# main.net
KiCad netlist of a schematic drawn in Altium Designer
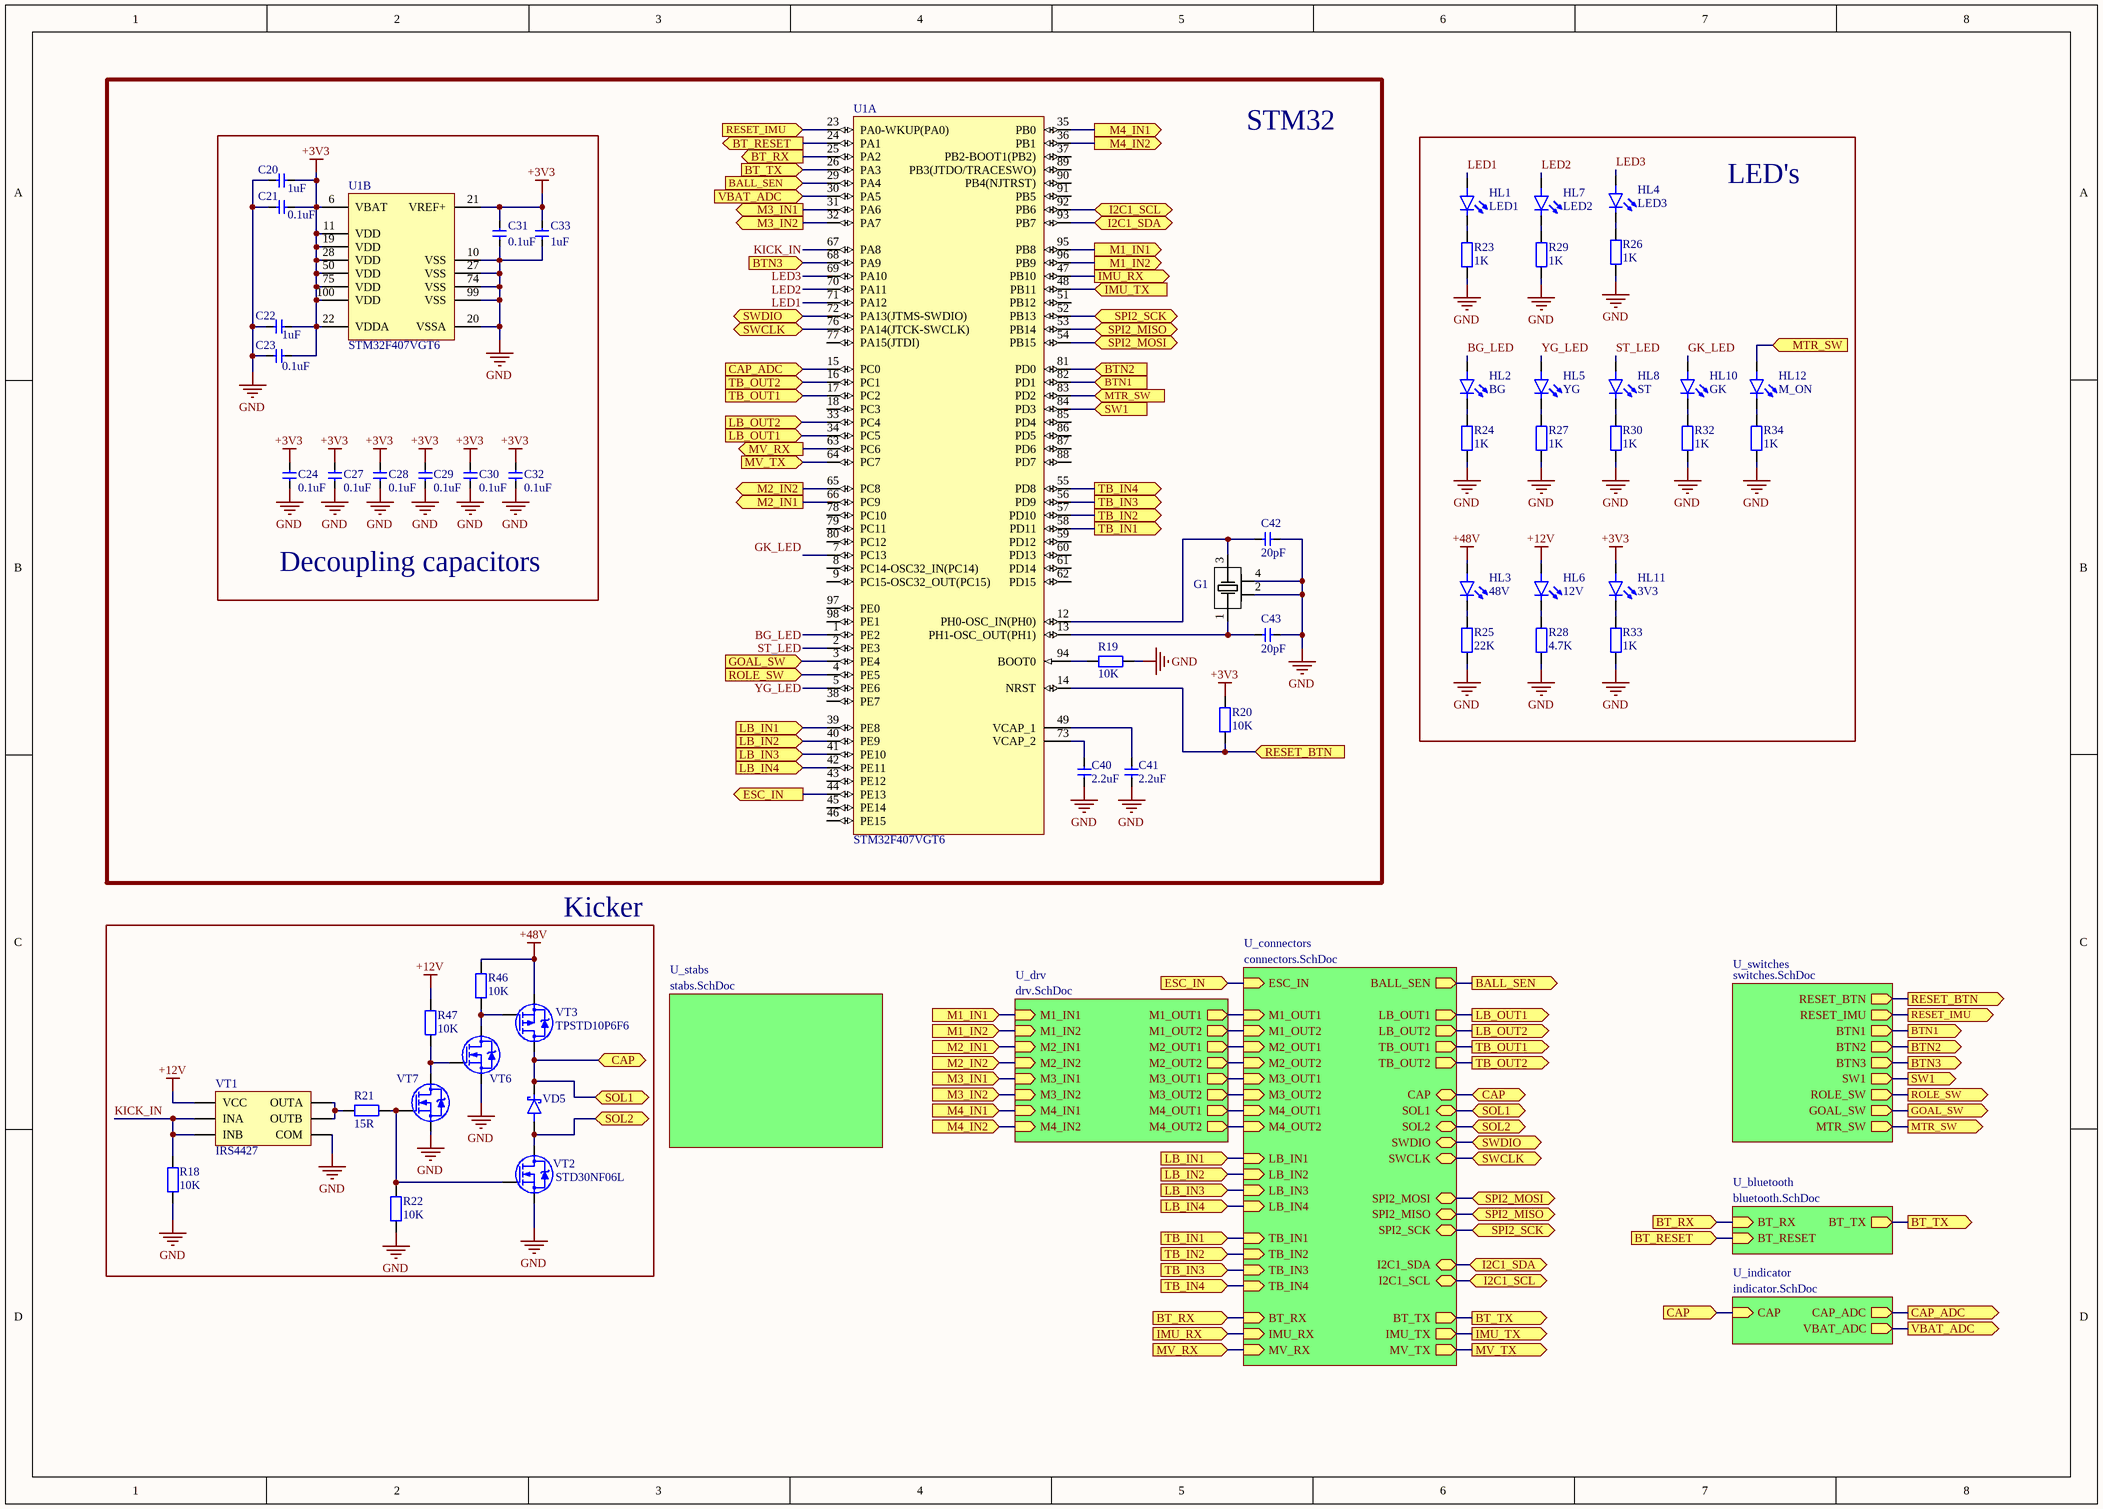
[diagram p0: main.SchDoc]

(export (version "E")
  (design (tool "Eeschema 10.0.6"))
  (components
    (comp (ref "C20")
      (value "1uF")
      (footprint "CAP0805")
      (description "Ceramic SMD Cap")
      (libsource (lib "Asterisk") (part "CAP Ceramic"))
    )
    (comp (ref "C21")
      (value "0.1uF")
      (footprint "CAP0805")
      (description "Ceramic SMD Cap")
      (libsource (lib "Asterisk") (part "CAP Ceramic"))
    )
    (comp (ref "C22")
      (value "1uF")
      (footprint "CAP0805")
      (description "Ceramic SMD Cap")
      (libsource (lib "Asterisk") (part "CAP Ceramic"))
    )
    (comp (ref "C23")
      (value "0.1uF")
      (footprint "CAP0805")
      (description "Ceramic SMD Cap")
      (libsource (lib "Asterisk") (part "CAP Ceramic"))
    )
    (comp (ref "C24")
      (value "0.1uF")
      (footprint "CAP0805")
      (description "Ceramic SMD Cap")
      (libsource (lib "Asterisk") (part "CAP Ceramic"))
    )
    (comp (ref "C27")
      (value "0.1uF")
      (footprint "CAP0805")
      (description "Ceramic SMD Cap")
      (libsource (lib "Asterisk") (part "CAP Ceramic"))
    )
    (comp (ref "C28")
      (value "0.1uF")
      (footprint "CAP0805")
      (description "Ceramic SMD Cap")
      (libsource (lib "Asterisk") (part "CAP Ceramic"))
    )
    (comp (ref "C29")
      (value "0.1uF")
      (footprint "CAP0805")
      (description "Ceramic SMD Cap")
      (libsource (lib "Asterisk") (part "CAP Ceramic"))
    )
    (comp (ref "C30")
      (value "0.1uF")
      (footprint "CAP0805")
      (description "Ceramic SMD Cap")
      (libsource (lib "Asterisk") (part "CAP Ceramic"))
    )
    (comp (ref "C31")
      (value "0.1uF")
      (footprint "CAP0805")
      (description "Ceramic SMD Cap")
      (libsource (lib "Asterisk") (part "CAP Ceramic"))
    )
    (comp (ref "C32")
      (value "0.1uF")
      (footprint "CAP0805")
      (description "Ceramic SMD Cap")
      (libsource (lib "Asterisk") (part "CAP Ceramic"))
    )
    (comp (ref "C33")
      (value "1uF")
      (footprint "CAP0805")
      (description "Ceramic SMD Cap")
      (libsource (lib "Asterisk") (part "CAP Ceramic"))
    )
    (comp (ref "C40")
      (value "2.2uF")
      (footprint "CAP0805")
      (description "Ceramic SMD Cap")
      (libsource (lib "") (part "CAP Ceramic_1"))
    )
    (comp (ref "C41")
      (value "2.2uF")
      (footprint "CAP0805")
      (description "Ceramic SMD Cap")
      (libsource (lib "") (part "CAP Ceramic_1"))
    )
    (comp (ref "C42")
      (value "20pF")
      (footprint "CAP0805")
      (description "Ceramic SMD Cap")
      (libsource (lib "Asterisk") (part "CAP Ceramic"))
    )
    (comp (ref "C43")
      (value "20pF")
      (footprint "CAP0805")
      (description "Ceramic SMD Cap")
      (libsource (lib "Asterisk") (part "CAP Ceramic"))
    )
    (comp (ref "G1")
      (value "8 MHz")
      (footprint "TSX-3225")
      (description "24MHz ±10ppm Crystal 9pF 40 Ohms 4-SMD, No Lead")
      (fields
        (field (name "PART NUMBER") "TSX-3225 24.0000MF15X-AC6")
        (field (name "DIGI-KEY PART NUMBER") "SER4180CT-ND")
      )
      (libsource (lib "SssAccesDatbase") (part "CTX957CT"))
    )
    (comp (ref "HL1")
      (value "LED1")
      (footprint "LED0603_WHITE")
      (description "LED smd")
      (libsource (lib "Asterisk") (part "LED"))
    )
    (comp (ref "HL2")
      (value "BG")
      (footprint "LED0603_WHITE")
      (description "LED smd")
      (libsource (lib "Asterisk") (part "LED"))
    )
    (comp (ref "HL3")
      (value "48V")
      (footprint "LED0603_GREEN")
      (description "LED smd")
      (libsource (lib "Asterisk") (part "LED"))
    )
    (comp (ref "HL4")
      (value "LED3")
      (footprint "LED0603_WHITE")
      (description "LED smd")
      (libsource (lib "Asterisk") (part "LED"))
    )
    (comp (ref "HL5")
      (value "YG")
      (footprint "LED0603_WHITE")
      (description "LED smd")
      (libsource (lib "Asterisk") (part "LED"))
    )
    (comp (ref "HL6")
      (value "12V")
      (footprint "LED0603_GREEN")
      (description "LED smd")
      (libsource (lib "Asterisk") (part "LED"))
    )
    (comp (ref "HL7")
      (value "LED2")
      (footprint "LED0603_WHITE")
      (description "LED smd")
      (libsource (lib "Asterisk") (part "LED"))
    )
    (comp (ref "HL8")
      (value "ST")
      (footprint "LED0603_WHITE")
      (description "LED smd")
      (libsource (lib "Asterisk") (part "LED"))
    )
    (comp (ref "HL10")
      (value "GK")
      (footprint "LED0603_WHITE")
      (description "LED smd")
      (libsource (lib "Asterisk") (part "LED"))
    )
    (comp (ref "HL11")
      (value "3V3")
      (footprint "LED0603_GREEN")
      (description "LED smd")
      (libsource (lib "Asterisk") (part "LED"))
    )
    (comp (ref "HL12")
      (value "M_ON")
      (footprint "LED0603_RED")
      (description "LED smd")
      (libsource (lib "Asterisk") (part "LED"))
    )
    (comp (ref "R18")
      (value "10K")
      (footprint "RES0805")
      (description "RES smd")
      (libsource (lib "Asterisk") (part "RES"))
    )
    (comp (ref "R19")
      (value "10K")
      (footprint "RES0805")
      (description "RES smd")
      (libsource (lib "Asterisk") (part "RES"))
    )
    (comp (ref "R20")
      (value "10K")
      (footprint "RES0805")
      (description "RES smd")
      (libsource (lib "Asterisk") (part "RES"))
    )
    (comp (ref "R21")
      (value "15R")
      (footprint "RES1206")
      (description "RES smd")
      (libsource (lib "Asterisk") (part "RES"))
    )
    (comp (ref "R22")
      (value "10K")
      (footprint "RES0805")
      (description "RES smd")
      (libsource (lib "Asterisk") (part "RES"))
    )
    (comp (ref "R23")
      (value "1K")
      (footprint "RES0805")
      (description "RES smd")
      (libsource (lib "Asterisk") (part "RES"))
    )
    (comp (ref "R24")
      (value "1K")
      (footprint "RES0805")
      (description "RES smd")
      (libsource (lib "Asterisk") (part "RES"))
    )
    (comp (ref "R25")
      (value "22K")
      (footprint "RES0805")
      (description "RES smd")
      (libsource (lib "Asterisk") (part "RES"))
    )
    (comp (ref "R26")
      (value "1K")
      (footprint "RES0805")
      (description "RES smd")
      (libsource (lib "Asterisk") (part "RES"))
    )
    (comp (ref "R27")
      (value "1K")
      (footprint "RES0805")
      (description "RES smd")
      (libsource (lib "Asterisk") (part "RES"))
    )
    (comp (ref "R28")
      (value "4.7K")
      (footprint "RES0805")
      (description "RES smd")
      (libsource (lib "Asterisk") (part "RES"))
    )
    (comp (ref "R29")
      (value "1K")
      (footprint "RES0805")
      (description "RES smd")
      (libsource (lib "Asterisk") (part "RES"))
    )
    (comp (ref "R30")
      (value "1K")
      (footprint "RES0805")
      (description "RES smd")
      (libsource (lib "Asterisk") (part "RES"))
    )
    (comp (ref "R32")
      (value "1K")
      (footprint "RES0805")
      (description "RES smd")
      (libsource (lib "Asterisk") (part "RES"))
    )
    (comp (ref "R33")
      (value "1K")
      (footprint "RES0805")
      (description "RES smd")
      (libsource (lib "Asterisk") (part "RES"))
    )
    (comp (ref "R34")
      (value "1K")
      (footprint "RES0805")
      (description "RES smd")
      (libsource (lib "Asterisk") (part "RES"))
    )
    (comp (ref "R46")
      (value "10K")
      (footprint "RES0805")
      (description "RES smd")
      (libsource (lib "Asterisk") (part "RES"))
    )
    (comp (ref "R47")
      (value "10K")
      (footprint "RES0805")
      (description "RES smd")
      (libsource (lib "Asterisk") (part "RES"))
    )
    (comp (ref "U1")
      (value "STM32F407VGT6")
      (footprint "LQFP100")
      (fields (field (name "MANUFACTURER") "STMicroelectronics"))
      (libsource (lib "Asterisk") (part "STM32F407VGT6"))
    )
    (comp (ref "VD5")
      (value "Diode Schottky")
      (footprint "DO-214AC (SMA)")
      (libsource (lib "Asterisk") (part "Diode Schottky"))
    )
    (comp (ref "VT1")
      (value "IRS4427")
      (footprint "SOIC-8")
      (description "Mosfet driver")
      (libsource (lib "Asterisk") (part "IRS4427"))
    )
    (comp (ref "VT2")
      (value "STD30NF06L")
      (footprint "DPAK")
      (description "N-MOSFET\r\nUds = 60 V\r\nIds = 30 A\r\nRds = 0.023 Ohm\r\nP = 55 W")
      (libsource (lib "Asterisk") (part "STD30NF06L"))
    )
    (comp (ref "VT3")
      (value "TPSTD10P6F6")
      (footprint "DPAK")
      (description "P-MOSFET\r\nUds = 60 V\r\nIds = 13 A\r\nRds = 0.100 Ohm\r\nP = 60 W")
      (libsource (lib "Asterisk") (part "TPSTD10P6F6"))
    )
    (comp (ref "VT6")
      (value "IRLML0060")
      (footprint "SOT-23-3")
      (description "N-MOSFET\r\nUds = 20 V\r\nIds = 4.2 A\r\nRds = 0.035 Ohm\r\nP = 8 W")
      (libsource (lib "Asterisk") (part "IRLML2502"))
    )
    (comp (ref "VT7")
      (value "IRLML0060")
      (footprint "SOT-23-3")
      (description "N-MOSFET\r\nUds = 20 V\r\nIds = 4.2 A\r\nRds = 0.035 Ohm\r\nP = 8 W")
      (libsource (lib "Asterisk") (part "IRLML2502"))
    )
  )
  (nets
    (net (code "1") (name "+3V3") (class "Default")
      (node (ref "C20") (pin "1") (pinfunction "1_1") (pintype "passive"))
      (node (ref "C21") (pin "1") (pinfunction "1_1") (pintype "passive"))
      (node (ref "C22") (pin "1") (pinfunction "1_1") (pintype "passive"))
      (node (ref "C23") (pin "1") (pinfunction "1_1") (pintype "passive"))
      (node (ref "C24") (pin "1") (pinfunction "1_1") (pintype "passive"))
      (node (ref "C27") (pin "1") (pinfunction "1_1") (pintype "passive"))
      (node (ref "C28") (pin "1") (pinfunction "1_1") (pintype "passive"))
      (node (ref "C29") (pin "1") (pinfunction "1_1") (pintype "passive"))
      (node (ref "C30") (pin "1") (pinfunction "1_1") (pintype "passive"))
      (node (ref "C31") (pin "2") (pinfunction "2_2") (pintype "passive"))
      (node (ref "C32") (pin "1") (pinfunction "1_1") (pintype "passive"))
      (node (ref "C33") (pin "2") (pinfunction "2_2") (pintype "passive"))
      (node (ref "HL11") (pin "2") (pinfunction "A_2") (pintype "passive"))
      (node (ref "R20") (pin "1") (pinfunction "1_1") (pintype "passive"))
      (node (ref "U1") (pin "100") (pinfunction "VDD_100") (pintype "power_in"))
      (node (ref "U1") (pin "11") (pinfunction "VDD_11") (pintype "power_in"))
      (node (ref "U1") (pin "19") (pinfunction "VDD_19") (pintype "power_in"))
      (node (ref "U1") (pin "21") (pinfunction "VREF+_21") (pintype "power_in"))
      (node (ref "U1") (pin "22") (pinfunction "VDDA_22") (pintype "power_in"))
      (node (ref "U1") (pin "28") (pinfunction "VDD_28") (pintype "power_in"))
      (node (ref "U1") (pin "50") (pinfunction "VDD_50") (pintype "power_in"))
      (node (ref "U1") (pin "6") (pinfunction "VBAT_6") (pintype "power_in"))
      (node (ref "U1") (pin "75") (pinfunction "VDD_75") (pintype "power_in"))
    )
    (net (code "2") (name "+12V") (class "Default")
      (node (ref "HL6") (pin "2") (pinfunction "A_2") (pintype "passive"))
      (node (ref "R47") (pin "2") (pinfunction "2_2") (pintype "passive"))
      (node (ref "VT1") (pin "6") (pinfunction "VCC_6") (pintype "passive"))
    )
    (net (code "3") (name "+48V") (class "Default")
      (node (ref "HL3") (pin "2") (pinfunction "A_2") (pintype "passive"))
      (node (ref "R46") (pin "2") (pinfunction "2_2") (pintype "passive"))
      (node (ref "VT3") (pin "S") (pinfunction "S_S") (pintype "passive"))
    )
    (net (code "4") (name "/BALL_SEN") (class "Default")
      (node (ref "U1") (pin "29") (pinfunction "PA4_29") (pintype "bidirectional"))
    )
    (net (code "5") (name "/BG_LED") (class "Default")
      (node (ref "HL2") (pin "2") (pinfunction "A_2") (pintype "passive"))
      (node (ref "U1") (pin "1") (pinfunction "PE2_1") (pintype "bidirectional"))
    )
    (net (code "6") (name "/BTN1") (class "Default")
      (node (ref "U1") (pin "82") (pinfunction "PD1_82") (pintype "bidirectional"))
    )
    (net (code "7") (name "/BTN2") (class "Default")
      (node (ref "U1") (pin "81") (pinfunction "PD0_81") (pintype "bidirectional"))
    )
    (net (code "8") (name "/BTN3") (class "Default")
      (node (ref "U1") (pin "68") (pinfunction "PA9_68") (pintype "bidirectional"))
    )
    (net (code "9") (name "/BT_RESET") (class "Default")
      (node (ref "U1") (pin "24") (pinfunction "PA1_24") (pintype "bidirectional"))
    )
    (net (code "10") (name "/BT_RX") (class "Default")
      (node (ref "U1") (pin "25") (pinfunction "PA2_25") (pintype "bidirectional"))
    )
    (net (code "11") (name "/BT_TX") (class "Default")
      (node (ref "U1") (pin "26") (pinfunction "PA3_26") (pintype "bidirectional"))
    )
    (net (code "12") (name "/CAP") (class "Default")
      (node (ref "VD5") (pin "K") (pinfunction "K_K") (pintype "passive"))
      (node (ref "VT3") (pin "D") (pinfunction "D_D") (pintype "passive"))
    )
    (net (code "13") (name "/CAP_ADC") (class "Default")
      (node (ref "U1") (pin "15") (pinfunction "PC0_15") (pintype "bidirectional"))
    )
    (net (code "14") (name "/ESC_IN") (class "Default")
      (node (ref "U1") (pin "44") (pinfunction "PE13_44") (pintype "bidirectional"))
    )
    (net (code "15") (name "/GK_LED") (class "Default")
      (node (ref "HL10") (pin "2") (pinfunction "A_2") (pintype "passive"))
      (node (ref "U1") (pin "7") (pinfunction "PC13_7") (pintype "bidirectional"))
    )
    (net (code "16") (name "/GOAL_SW") (class "Default")
      (node (ref "U1") (pin "3") (pinfunction "PE4_3") (pintype "bidirectional"))
    )
    (net (code "17") (name "/I2C1_SCL") (class "Default")
      (node (ref "U1") (pin "92") (pinfunction "PB6_92") (pintype "bidirectional"))
    )
    (net (code "18") (name "/I2C1_SDA") (class "Default")
      (node (ref "U1") (pin "93") (pinfunction "PB7_93") (pintype "bidirectional"))
    )
    (net (code "19") (name "/IMU_RX") (class "Default")
      (node (ref "U1") (pin "47") (pinfunction "PB10_47") (pintype "bidirectional"))
    )
    (net (code "20") (name "/IMU_TX") (class "Default")
      (node (ref "U1") (pin "48") (pinfunction "PB11_48") (pintype "bidirectional"))
    )
    (net (code "21") (name "/KICK_IN") (class "Default")
      (node (ref "R18") (pin "2") (pinfunction "2_2") (pintype "passive"))
      (node (ref "U1") (pin "67") (pinfunction "PA8_67") (pintype "bidirectional"))
      (node (ref "VT1") (pin "2") (pinfunction "INA_2") (pintype "passive"))
      (node (ref "VT1") (pin "4") (pinfunction "INB_4") (pintype "passive"))
    )
    (net (code "22") (name "/LB_IN1") (class "Default")
      (node (ref "U1") (pin "39") (pinfunction "PE8_39") (pintype "bidirectional"))
    )
    (net (code "23") (name "/LB_IN2") (class "Default")
      (node (ref "U1") (pin "40") (pinfunction "PE9_40") (pintype "bidirectional"))
    )
    (net (code "24") (name "/LB_IN3") (class "Default")
      (node (ref "U1") (pin "41") (pinfunction "PE10_41") (pintype "bidirectional"))
    )
    (net (code "25") (name "/LB_IN4") (class "Default")
      (node (ref "U1") (pin "42") (pinfunction "PE11_42") (pintype "bidirectional"))
    )
    (net (code "26") (name "/LB_OUT1") (class "Default")
      (node (ref "U1") (pin "34") (pinfunction "PC5_34") (pintype "bidirectional"))
    )
    (net (code "27") (name "/LB_OUT2") (class "Default")
      (node (ref "U1") (pin "33") (pinfunction "PC4_33") (pintype "bidirectional"))
    )
    (net (code "28") (name "/LED1") (class "Default")
      (node (ref "HL1") (pin "2") (pinfunction "A_2") (pintype "passive"))
      (node (ref "U1") (pin "71") (pinfunction "PA12_71") (pintype "bidirectional"))
    )
    (net (code "29") (name "/LED2") (class "Default")
      (node (ref "HL7") (pin "2") (pinfunction "A_2") (pintype "passive"))
      (node (ref "U1") (pin "70") (pinfunction "PA11_70") (pintype "bidirectional"))
    )
    (net (code "30") (name "/LED3") (class "Default")
      (node (ref "HL4") (pin "2") (pinfunction "A_2") (pintype "passive"))
      (node (ref "U1") (pin "69") (pinfunction "PA10_69") (pintype "bidirectional"))
    )
    (net (code "31") (name "/M1_IN1") (class "Default")
      (node (ref "U1") (pin "95") (pinfunction "PB8_95") (pintype "bidirectional"))
    )
    (net (code "32") (name "/M1_IN2") (class "Default")
      (node (ref "U1") (pin "96") (pinfunction "PB9_96") (pintype "bidirectional"))
    )
    (net (code "35") (name "/M2_IN1") (class "Default")
      (node (ref "U1") (pin "66") (pinfunction "PC9_66") (pintype "bidirectional"))
    )
    (net (code "36") (name "/M2_IN2") (class "Default")
      (node (ref "U1") (pin "65") (pinfunction "PC8_65") (pintype "bidirectional"))
    )
    (net (code "39") (name "/M3_IN1") (class "Default")
      (node (ref "U1") (pin "31") (pinfunction "PA6_31") (pintype "bidirectional"))
    )
    (net (code "40") (name "/M3_IN2") (class "Default")
      (node (ref "U1") (pin "32") (pinfunction "PA7_32") (pintype "bidirectional"))
    )
    (net (code "43") (name "/M4_IN1") (class "Default")
      (node (ref "U1") (pin "35") (pinfunction "PB0_35") (pintype "bidirectional"))
    )
    (net (code "44") (name "/M4_IN2") (class "Default")
      (node (ref "U1") (pin "36") (pinfunction "PB1_36") (pintype "bidirectional"))
    )
    (net (code "47") (name "/MTR_SW") (class "Default")
      (node (ref "HL12") (pin "2") (pinfunction "A_2") (pintype "passive"))
      (node (ref "U1") (pin "83") (pinfunction "PD2_83") (pintype "bidirectional"))
    )
    (net (code "48") (name "/MV_RX") (class "Default")
      (node (ref "U1") (pin "63") (pinfunction "PC6_63") (pintype "bidirectional"))
    )
    (net (code "49") (name "/MV_TX") (class "Default")
      (node (ref "U1") (pin "64") (pinfunction "PC7_64") (pintype "bidirectional"))
    )
    (net (code "50") (name "/RESET_BTN") (class "Default")
      (node (ref "R20") (pin "2") (pinfunction "2_2") (pintype "passive"))
      (node (ref "U1") (pin "14") (pinfunction "NRST_14") (pintype "bidirectional"))
    )
    (net (code "51") (name "/RESET_IMU") (class "Default")
      (node (ref "U1") (pin "23") (pinfunction "PA0-WKUP(PA0)_23") (pintype "bidirectional"))
    )
    (net (code "52") (name "/ROLE_SW") (class "Default")
      (node (ref "U1") (pin "4") (pinfunction "PE5_4") (pintype "bidirectional"))
    )
    (net (code "53") (name "/SOL2") (class "Default")
      (node (ref "VD5") (pin "A") (pinfunction "A_A") (pintype "passive"))
      (node (ref "VT2") (pin "D") (pinfunction "D_D") (pintype "passive"))
    )
    (net (code "54") (name "/SPI2_MISO") (class "Default")
      (node (ref "U1") (pin "53") (pinfunction "PB14_53") (pintype "bidirectional"))
    )
    (net (code "55") (name "/SPI2_MOSI") (class "Default")
      (node (ref "U1") (pin "54") (pinfunction "PB15_54") (pintype "bidirectional"))
    )
    (net (code "56") (name "/SPI2_SCK") (class "Default")
      (node (ref "U1") (pin "52") (pinfunction "PB13_52") (pintype "bidirectional"))
    )
    (net (code "57") (name "/ST_LED") (class "Default")
      (node (ref "HL8") (pin "2") (pinfunction "A_2") (pintype "passive"))
      (node (ref "U1") (pin "2") (pinfunction "PE3_2") (pintype "bidirectional"))
    )
    (net (code "58") (name "/SW1") (class "Default")
      (node (ref "U1") (pin "84") (pinfunction "PD3_84") (pintype "bidirectional"))
    )
    (net (code "59") (name "/SWCLK") (class "Default")
      (node (ref "U1") (pin "76") (pinfunction "PA14(JTCK-SWCLK)_76") (pintype "bidirectional"))
    )
    (net (code "60") (name "/SWDIO") (class "Default")
      (node (ref "U1") (pin "72") (pinfunction "PA13(JTMS-SWDIO)_72") (pintype "bidirectional"))
    )
    (net (code "61") (name "/TB_IN1") (class "Default")
      (node (ref "U1") (pin "58") (pinfunction "PD11_58") (pintype "bidirectional"))
    )
    (net (code "62") (name "/TB_IN2") (class "Default")
      (node (ref "U1") (pin "57") (pinfunction "PD10_57") (pintype "bidirectional"))
    )
    (net (code "63") (name "/TB_IN3") (class "Default")
      (node (ref "U1") (pin "56") (pinfunction "PD9_56") (pintype "bidirectional"))
    )
    (net (code "64") (name "/TB_IN4") (class "Default")
      (node (ref "U1") (pin "55") (pinfunction "PD8_55") (pintype "bidirectional"))
    )
    (net (code "65") (name "/TB_OUT1") (class "Default")
      (node (ref "U1") (pin "17") (pinfunction "PC2_17") (pintype "bidirectional"))
    )
    (net (code "66") (name "/TB_OUT2") (class "Default")
      (node (ref "U1") (pin "16") (pinfunction "PC1_16") (pintype "bidirectional"))
    )
    (net (code "67") (name "/VBAT_ADC") (class "Default")
      (node (ref "U1") (pin "30") (pinfunction "PA5_30") (pintype "bidirectional"))
    )
    (net (code "68") (name "/YG_LED") (class "Default")
      (node (ref "HL5") (pin "2") (pinfunction "A_2") (pintype "passive"))
      (node (ref "U1") (pin "5") (pinfunction "PE6_5") (pintype "bidirectional"))
    )
    (net (code "69") (name "GND") (class "Default")
      (node (ref "C20") (pin "2") (pinfunction "2_2") (pintype "passive"))
      (node (ref "C21") (pin "2") (pinfunction "2_2") (pintype "passive"))
      (node (ref "C22") (pin "2") (pinfunction "2_2") (pintype "passive"))
      (node (ref "C23") (pin "2") (pinfunction "2_2") (pintype "passive"))
      (node (ref "C24") (pin "2") (pinfunction "2_2") (pintype "passive"))
      (node (ref "C27") (pin "2") (pinfunction "2_2") (pintype "passive"))
      (node (ref "C28") (pin "2") (pinfunction "2_2") (pintype "passive"))
      (node (ref "C29") (pin "2") (pinfunction "2_2") (pintype "passive"))
      (node (ref "C30") (pin "2") (pinfunction "2_2") (pintype "passive"))
      (node (ref "C31") (pin "1") (pinfunction "1_1") (pintype "passive"))
      (node (ref "C32") (pin "2") (pinfunction "2_2") (pintype "passive"))
      (node (ref "C33") (pin "1") (pinfunction "1_1") (pintype "passive"))
      (node (ref "C40") (pin "1") (pinfunction "1_1") (pintype "passive"))
      (node (ref "C41") (pin "1") (pinfunction "1_1") (pintype "passive"))
      (node (ref "C42") (pin "2") (pinfunction "2_2") (pintype "passive"))
      (node (ref "C43") (pin "2") (pinfunction "2_2") (pintype "passive"))
      (node (ref "G1") (pin "2") (pinfunction "2_2") (pintype "passive"))
      (node (ref "G1") (pin "4") (pinfunction "4_4") (pintype "passive"))
      (node (ref "R18") (pin "1") (pinfunction "1_1") (pintype "passive"))
      (node (ref "R19") (pin "1") (pinfunction "1_1") (pintype "passive"))
      (node (ref "R22") (pin "1") (pinfunction "1_1") (pintype "passive"))
      (node (ref "R23") (pin "1") (pinfunction "1_1") (pintype "passive"))
      (node (ref "R24") (pin "1") (pinfunction "1_1") (pintype "passive"))
      (node (ref "R25") (pin "1") (pinfunction "1_1") (pintype "passive"))
      (node (ref "R26") (pin "1") (pinfunction "1_1") (pintype "passive"))
      (node (ref "R27") (pin "1") (pinfunction "1_1") (pintype "passive"))
      (node (ref "R28") (pin "1") (pinfunction "1_1") (pintype "passive"))
      (node (ref "R29") (pin "1") (pinfunction "1_1") (pintype "passive"))
      (node (ref "R30") (pin "1") (pinfunction "1_1") (pintype "passive"))
      (node (ref "R32") (pin "1") (pinfunction "1_1") (pintype "passive"))
      (node (ref "R33") (pin "1") (pinfunction "1_1") (pintype "passive"))
      (node (ref "R34") (pin "1") (pinfunction "1_1") (pintype "passive"))
      (node (ref "U1") (pin "10") (pinfunction "VSS_10") (pintype "power_in"))
      (node (ref "U1") (pin "20") (pinfunction "VSSA_20") (pintype "power_in"))
      (node (ref "U1") (pin "27") (pinfunction "VSS_27") (pintype "power_in"))
      (node (ref "U1") (pin "74") (pinfunction "VSS_74") (pintype "power_in"))
      (node (ref "U1") (pin "99") (pinfunction "VSS_99") (pintype "power_in"))
      (node (ref "VT1") (pin "3") (pinfunction "COM_3") (pintype "passive"))
      (node (ref "VT2") (pin "S") (pinfunction "S_S") (pintype "passive"))
      (node (ref "VT6") (pin "S") (pinfunction "S_S") (pintype "passive"))
      (node (ref "VT7") (pin "S") (pinfunction "S_S") (pintype "passive"))
    )
    (net (code "70") (name "Net-(HL1-K)") (class "Default")
      (node (ref "HL1") (pin "1") (pinfunction "K_1") (pintype "passive"))
      (node (ref "R23") (pin "2") (pinfunction "2_2") (pintype "passive"))
    )
    (net (code "71") (name "Net-(HL2-K)") (class "Default")
      (node (ref "HL2") (pin "1") (pinfunction "K_1") (pintype "passive"))
      (node (ref "R24") (pin "2") (pinfunction "2_2") (pintype "passive"))
    )
    (net (code "72") (name "Net-(HL3-K)") (class "Default")
      (node (ref "HL3") (pin "1") (pinfunction "K_1") (pintype "passive"))
      (node (ref "R25") (pin "2") (pinfunction "2_2") (pintype "passive"))
    )
    (net (code "73") (name "Net-(HL4-K)") (class "Default")
      (node (ref "HL4") (pin "1") (pinfunction "K_1") (pintype "passive"))
      (node (ref "R26") (pin "2") (pinfunction "2_2") (pintype "passive"))
    )
    (net (code "74") (name "Net-(HL5-K)") (class "Default")
      (node (ref "HL5") (pin "1") (pinfunction "K_1") (pintype "passive"))
      (node (ref "R27") (pin "2") (pinfunction "2_2") (pintype "passive"))
    )
    (net (code "75") (name "Net-(HL6-K)") (class "Default")
      (node (ref "HL6") (pin "1") (pinfunction "K_1") (pintype "passive"))
      (node (ref "R28") (pin "2") (pinfunction "2_2") (pintype "passive"))
    )
    (net (code "76") (name "Net-(HL7-K)") (class "Default")
      (node (ref "HL7") (pin "1") (pinfunction "K_1") (pintype "passive"))
      (node (ref "R29") (pin "2") (pinfunction "2_2") (pintype "passive"))
    )
    (net (code "77") (name "Net-(HL8-K)") (class "Default")
      (node (ref "HL8") (pin "1") (pinfunction "K_1") (pintype "passive"))
      (node (ref "R30") (pin "2") (pinfunction "2_2") (pintype "passive"))
    )
    (net (code "78") (name "Net-(HL10-K)") (class "Default")
      (node (ref "HL10") (pin "1") (pinfunction "K_1") (pintype "passive"))
      (node (ref "R32") (pin "2") (pinfunction "2_2") (pintype "passive"))
    )
    (net (code "79") (name "Net-(HL11-K)") (class "Default")
      (node (ref "HL11") (pin "1") (pinfunction "K_1") (pintype "passive"))
      (node (ref "R33") (pin "2") (pinfunction "2_2") (pintype "passive"))
    )
    (net (code "80") (name "Net-(HL12-K)") (class "Default")
      (node (ref "HL12") (pin "1") (pinfunction "K_1") (pintype "passive"))
      (node (ref "R34") (pin "2") (pinfunction "2_2") (pintype "passive"))
    )
    (net (code "81") (name "Net-(R21-Pad2)") (class "Default")
      (node (ref "R21") (pin "2") (pinfunction "2_2") (pintype "passive"))
      (node (ref "R22") (pin "2") (pinfunction "2_2") (pintype "passive"))
      (node (ref "VT2") (pin "G") (pinfunction "G_G") (pintype "passive"))
      (node (ref "VT7") (pin "G") (pinfunction "G_G") (pintype "passive"))
    )
    (net (code "82") (name "Net-(R46-Pad1)") (class "Default")
      (node (ref "R46") (pin "1") (pinfunction "1_1") (pintype "passive"))
      (node (ref "VT3") (pin "G") (pinfunction "G_G") (pintype "passive"))
      (node (ref "VT6") (pin "D") (pinfunction "D_D") (pintype "passive"))
    )
    (net (code "83") (name "Net-(R47-Pad1)") (class "Default")
      (node (ref "R47") (pin "1") (pinfunction "1_1") (pintype "passive"))
      (node (ref "VT6") (pin "G") (pinfunction "G_G") (pintype "passive"))
      (node (ref "VT7") (pin "D") (pinfunction "D_D") (pintype "passive"))
    )
    (net (code "84") (name "Net-(U1A-BOOT0)") (class "Default")
      (node (ref "R19") (pin "2") (pinfunction "2_2") (pintype "passive"))
      (node (ref "U1") (pin "94") (pinfunction "BOOT0_94") (pintype "input"))
    )
    (net (code "85") (name "Net-(U1A-PH0-OSC_IN(PH0))") (class "Default")
      (node (ref "C42") (pin "1") (pinfunction "1_1") (pintype "passive"))
      (node (ref "G1") (pin "3") (pinfunction "3_3") (pintype "passive"))
      (node (ref "U1") (pin "12") (pinfunction "PH0-OSC_IN(PH0)_12") (pintype "bidirectional"))
    )
    (net (code "86") (name "Net-(U1A-PH1-OSC_OUT(PH1))") (class "Default")
      (node (ref "C43") (pin "1") (pinfunction "1_1") (pintype "passive"))
      (node (ref "G1") (pin "1") (pinfunction "1_1") (pintype "passive"))
      (node (ref "U1") (pin "13") (pinfunction "PH1-OSC_OUT(PH1)_13") (pintype "bidirectional"))
    )
    (net (code "87") (name "Net-(U1A-VCAP_1)") (class "Default")
      (node (ref "C41") (pin "2") (pinfunction "2_2") (pintype "passive"))
      (node (ref "U1") (pin "49") (pinfunction "VCAP_1_49") (pintype "power_in"))
    )
    (net (code "88") (name "Net-(U1A-VCAP_2)") (class "Default")
      (node (ref "C40") (pin "2") (pinfunction "2_2") (pintype "passive"))
      (node (ref "U1") (pin "73") (pinfunction "VCAP_2_73") (pintype "power_in"))
    )
    (net (code "89") (name "Net-(VT1-OUTA)") (class "Default")
      (node (ref "R21") (pin "1") (pinfunction "1_1") (pintype "passive"))
      (node (ref "VT1") (pin "5") (pinfunction "OUTB_5") (pintype "passive"))
      (node (ref "VT1") (pin "7") (pinfunction "OUTA_7") (pintype "passive"))
    )
    (net (code "90") (name "unconnected-(U1A-PA15(JTDI)-Pad77)") (class "Default")
      (node (ref "U1") (pin "77") (pinfunction "PA15(JTDI)_77") (pintype "bidirectional"))
    )
    (net (code "91") (name "unconnected-(U1A-PB2-BOOT1(PB2)-Pad37)") (class "Default")
      (node (ref "U1") (pin "37") (pinfunction "PB2-BOOT1(PB2)_37") (pintype "bidirectional"))
    )
    (net (code "92") (name "unconnected-(U1A-PB3(JTDO{slash}TRACESWO)-Pad89)") (class "Default")
      (node (ref "U1") (pin "89") (pinfunction "PB3(JTDO/TRACESWO)_89") (pintype "bidirectional"))
    )
    (net (code "93") (name "unconnected-(U1A-PB4(NJTRST)-Pad90)") (class "Default")
      (node (ref "U1") (pin "90") (pinfunction "PB4(NJTRST)_90") (pintype "bidirectional"))
    )
    (net (code "94") (name "unconnected-(U1A-PB5-Pad91)") (class "Default")
      (node (ref "U1") (pin "91") (pinfunction "PB5_91") (pintype "bidirectional"))
    )
    (net (code "95") (name "unconnected-(U1A-PB12-Pad51)") (class "Default")
      (node (ref "U1") (pin "51") (pinfunction "PB12_51") (pintype "bidirectional"))
    )
    (net (code "96") (name "unconnected-(U1A-PC3-Pad18)") (class "Default")
      (node (ref "U1") (pin "18") (pinfunction "PC3_18") (pintype "bidirectional"))
    )
    (net (code "97") (name "unconnected-(U1A-PC10-Pad78)") (class "Default")
      (node (ref "U1") (pin "78") (pinfunction "PC10_78") (pintype "bidirectional"))
    )
    (net (code "98") (name "unconnected-(U1A-PC11-Pad79)") (class "Default")
      (node (ref "U1") (pin "79") (pinfunction "PC11_79") (pintype "bidirectional"))
    )
    (net (code "99") (name "unconnected-(U1A-PC12-Pad80)") (class "Default")
      (node (ref "U1") (pin "80") (pinfunction "PC12_80") (pintype "bidirectional"))
    )
    (net (code "100") (name "unconnected-(U1A-PC14-OSC32_IN(PC14)-Pad8)") (class "Default")
      (node (ref "U1") (pin "8") (pinfunction "PC14-OSC32_IN(PC14)_8") (pintype "bidirectional"))
    )
    (net (code "101") (name "unconnected-(U1A-PC15-OSC32_OUT(PC15)-Pad9)") (class "Default")
      (node (ref "U1") (pin "9") (pinfunction "PC15-OSC32_OUT(PC15)_9") (pintype "bidirectional"))
    )
    (net (code "102") (name "unconnected-(U1A-PD4-Pad85)") (class "Default")
      (node (ref "U1") (pin "85") (pinfunction "PD4_85") (pintype "bidirectional"))
    )
    (net (code "103") (name "unconnected-(U1A-PD5-Pad86)") (class "Default")
      (node (ref "U1") (pin "86") (pinfunction "PD5_86") (pintype "bidirectional"))
    )
    (net (code "104") (name "unconnected-(U1A-PD6-Pad87)") (class "Default")
      (node (ref "U1") (pin "87") (pinfunction "PD6_87") (pintype "bidirectional"))
    )
    (net (code "105") (name "unconnected-(U1A-PD7-Pad88)") (class "Default")
      (node (ref "U1") (pin "88") (pinfunction "PD7_88") (pintype "bidirectional"))
    )
    (net (code "106") (name "unconnected-(U1A-PD12-Pad59)") (class "Default")
      (node (ref "U1") (pin "59") (pinfunction "PD12_59") (pintype "bidirectional"))
    )
    (net (code "107") (name "unconnected-(U1A-PD13-Pad60)") (class "Default")
      (node (ref "U1") (pin "60") (pinfunction "PD13_60") (pintype "bidirectional"))
    )
    (net (code "108") (name "unconnected-(U1A-PD14-Pad61)") (class "Default")
      (node (ref "U1") (pin "61") (pinfunction "PD14_61") (pintype "bidirectional"))
    )
    (net (code "109") (name "unconnected-(U1A-PD15-Pad62)") (class "Default")
      (node (ref "U1") (pin "62") (pinfunction "PD15_62") (pintype "bidirectional"))
    )
    (net (code "110") (name "unconnected-(U1A-PE0-Pad97)") (class "Default")
      (node (ref "U1") (pin "97") (pinfunction "PE0_97") (pintype "bidirectional"))
    )
    (net (code "111") (name "unconnected-(U1A-PE1-Pad98)") (class "Default")
      (node (ref "U1") (pin "98") (pinfunction "PE1_98") (pintype "bidirectional"))
    )
    (net (code "112") (name "unconnected-(U1A-PE7-Pad38)") (class "Default")
      (node (ref "U1") (pin "38") (pinfunction "PE7_38") (pintype "bidirectional"))
    )
    (net (code "113") (name "unconnected-(U1A-PE12-Pad43)") (class "Default")
      (node (ref "U1") (pin "43") (pinfunction "PE12_43") (pintype "bidirectional"))
    )
    (net (code "114") (name "unconnected-(U1A-PE14-Pad45)") (class "Default")
      (node (ref "U1") (pin "45") (pinfunction "PE14_45") (pintype "bidirectional"))
    )
    (net (code "115") (name "unconnected-(U1A-PE15-Pad46)") (class "Default")
      (node (ref "U1") (pin "46") (pinfunction "PE15_46") (pintype "bidirectional"))
    )
  )
)
